# pas_pot_diff.net
KiCad netlist of a schematic drawn in EAGLE
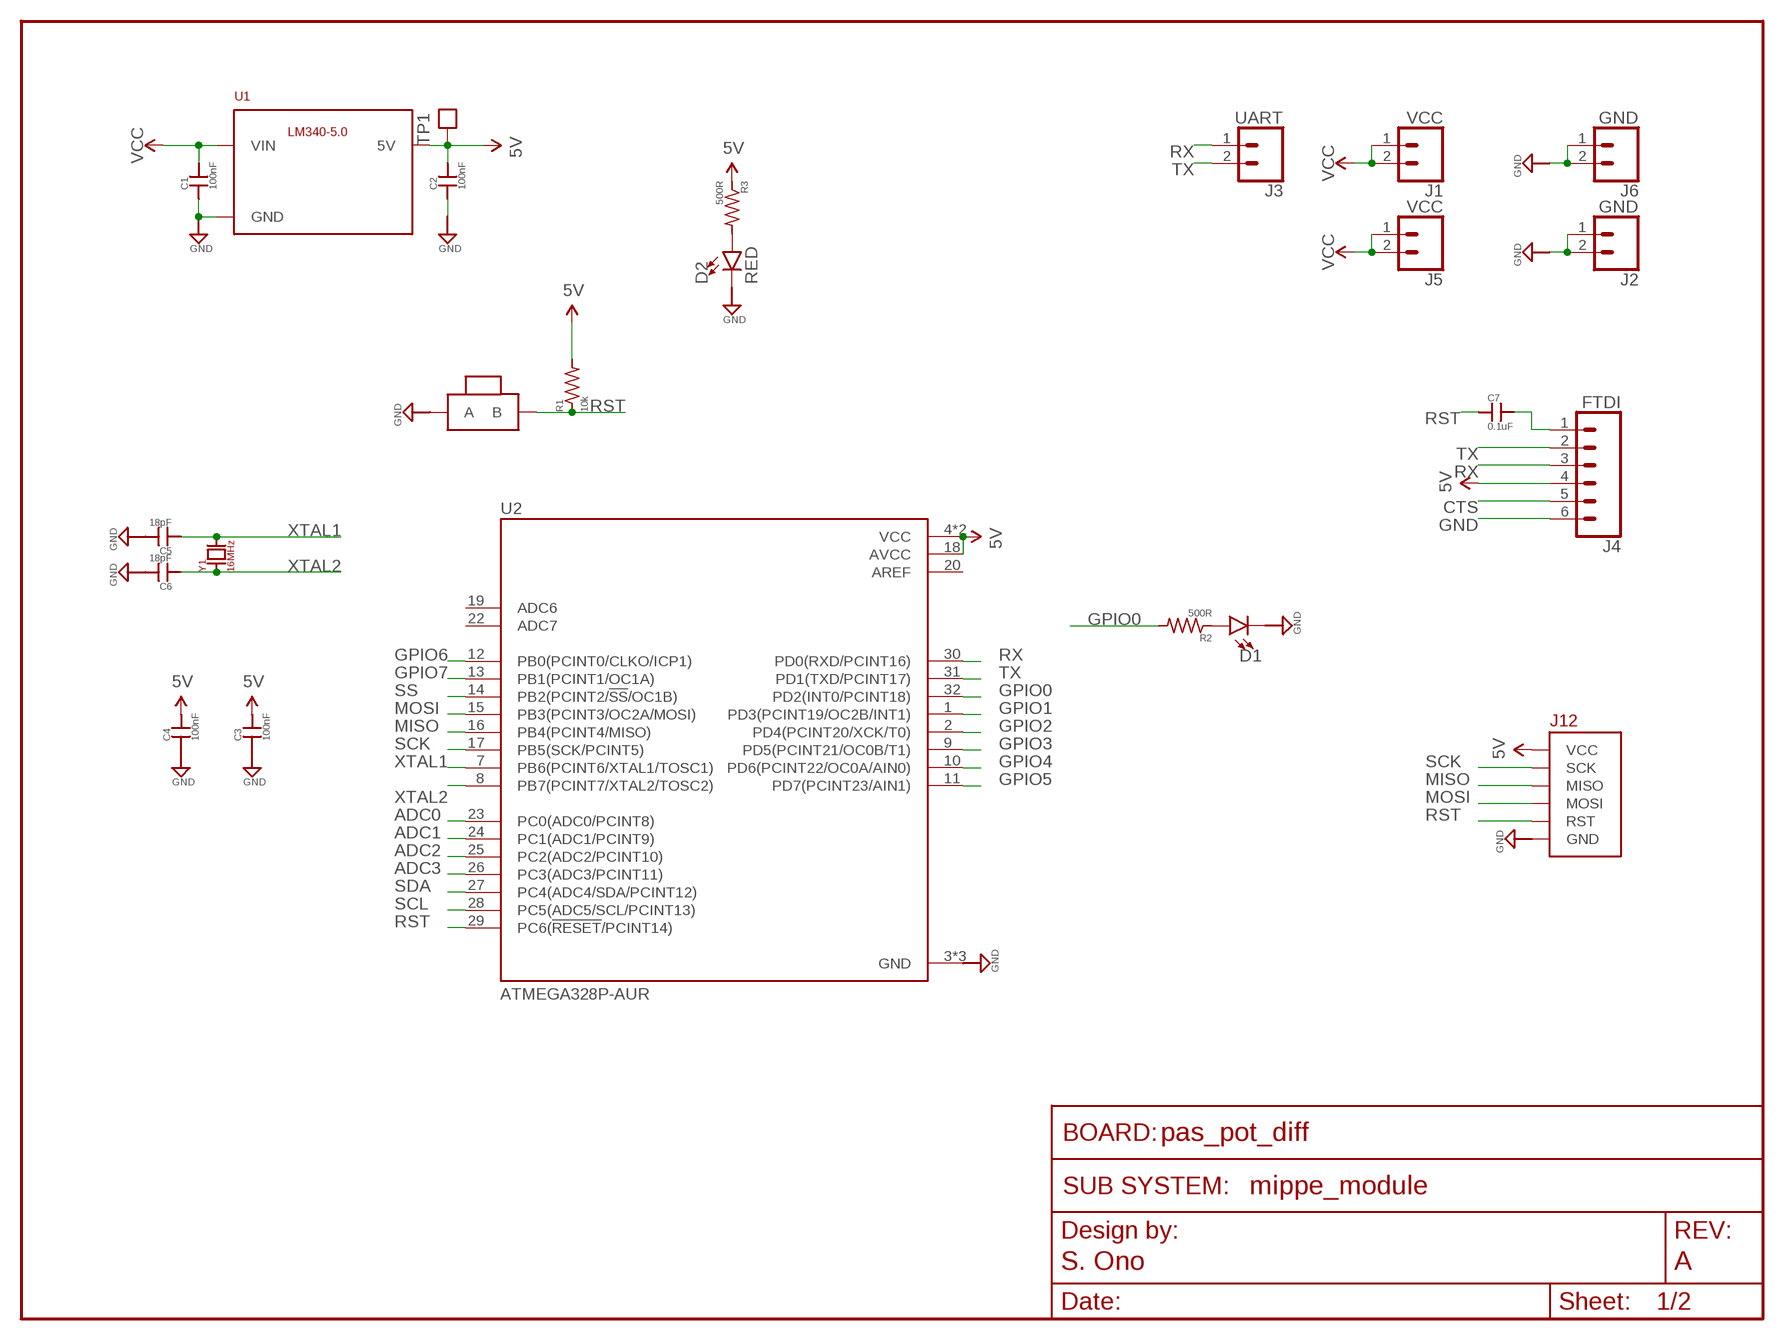
[diagram p0: schematic, sheet 1]
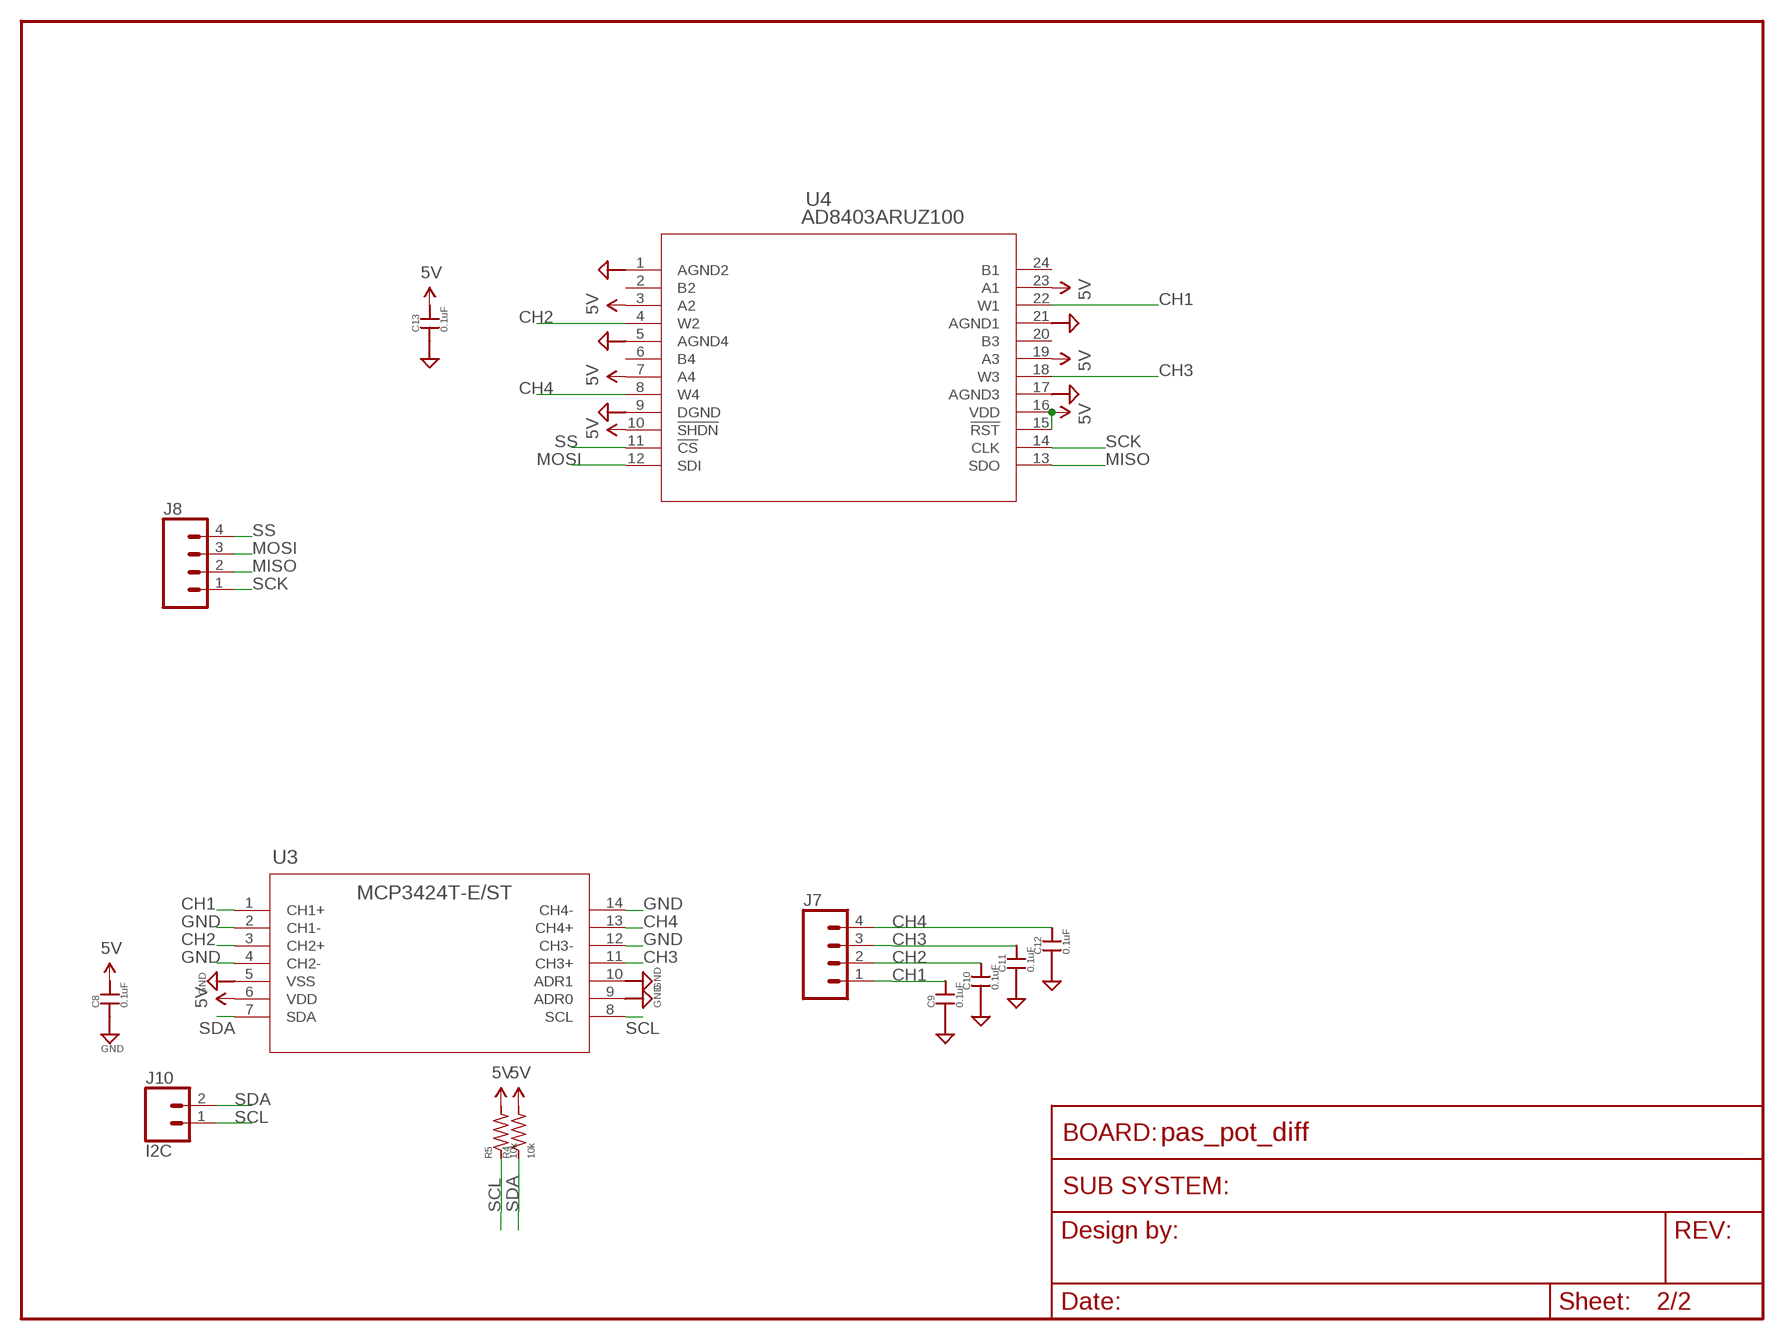
[diagram p1: schematic, sheet 2]

(export (version "E")
  (design (tool "Eeschema 10.0.6"))
  (components
    (comp (ref "C8")
      (value "0.1uF")
      (footprint "eagle-import:0402-CAP")
      (libsource (lib "eagle-import") (part "CAP0402-CAP"))
    )
    (comp (ref "C9")
      (value "0.1uF")
      (footprint "eagle-import:0402-CAP")
      (libsource (lib "eagle-import") (part "CAP0402-CAP"))
    )
    (comp (ref "C10")
      (value "0.1uF")
      (footprint "eagle-import:0402-CAP")
      (libsource (lib "eagle-import") (part "CAP0402-CAP"))
    )
    (comp (ref "C11")
      (value "0.1uF")
      (footprint "eagle-import:0402-CAP")
      (libsource (lib "eagle-import") (part "CAP0402-CAP"))
    )
    (comp (ref "C12")
      (value "0.1uF")
      (footprint "eagle-import:0402-CAP")
      (libsource (lib "eagle-import") (part "CAP0402-CAP"))
    )
    (comp (ref "C13")
      (value "0.1uF")
      (footprint "eagle-import:0402-CAP")
      (libsource (lib "eagle-import") (part "CAP0402-CAP"))
    )
    (comp (ref "J7")
      (value "CONN_04")
      (footprint "eagle-import:1X04")
      (libsource (lib "eagle-import") (part "CONN_04"))
    )
    (comp (ref "J8")
      (value "CONN_04")
      (footprint "eagle-import:1X04")
      (libsource (lib "eagle-import") (part "CONN_04"))
    )
    (comp (ref "J10")
      (value "I2C")
      (footprint "eagle-import:1X02")
      (libsource (lib "eagle-import") (part "CONN_02"))
    )
    (comp (ref "R4")
      (value "10k")
      (footprint "eagle-import:R0402")
      (libsource (lib "eagle-import") (part "R-US_R0402"))
    )
    (comp (ref "R5")
      (value "10k")
      (footprint "eagle-import:R0402")
      (libsource (lib "eagle-import") (part "R-US_R0402"))
    )
    (comp (ref "U3")
      (value "MCP3424T-E/ST")
      (footprint "eagle-import:TSSOP14_MC")
      (fields (field (name "MANUFACTURER_PART_NUMBER") "MCP3424TEST"))
      (libsource (lib "eagle-import") (part "MCP3424T-E/ST"))
    )
    (comp (ref "U4")
      (value "AD8403ARUZ100")
      (footprint "eagle-import:RU_24")
      (libsource (lib "eagle-import") (part "AD8403ARUZ100"))
    )
    (comp (ref "C1")
      (value "100nF")
      (footprint "eagle-import:0402-CAP")
      (libsource (lib "eagle-import") (part "CAP0402-CAP"))
    )
    (comp (ref "C2")
      (value "100nF")
      (footprint "eagle-import:0402-CAP")
      (libsource (lib "eagle-import") (part "CAP0402-CAP"))
    )
    (comp (ref "C3")
      (value "100nF")
      (footprint "eagle-import:0402-CAP")
      (libsource (lib "eagle-import") (part "CAP0402-CAP"))
    )
    (comp (ref "C4")
      (value "100nF")
      (footprint "eagle-import:0402-CAP")
      (libsource (lib "eagle-import") (part "CAP0402-CAP"))
    )
    (comp (ref "C5")
      (value "18pF")
      (footprint "eagle-import:0402-CAP")
      (libsource (lib "eagle-import") (part "CAP0402-CAP"))
    )
    (comp (ref "C6")
      (value "18pF")
      (footprint "eagle-import:0402-CAP")
      (libsource (lib "eagle-import") (part "CAP0402-CAP"))
    )
    (comp (ref "C7")
      (value "0.1uF")
      (footprint "eagle-import:0402-CAP")
      (libsource (lib "eagle-import") (part "CAP0402-CAP"))
    )
    (comp (ref "D1")
      (value "LED0603")
      (footprint "eagle-import:LED-0603")
      (libsource (lib "eagle-import") (part "LED0603"))
    )
    (comp (ref "D2")
      (value "RED")
      (footprint "eagle-import:LED-0603")
      (libsource (lib "eagle-import") (part "LED0603"))
    )
    (comp (ref "J1")
      (value "VCC")
      (footprint "eagle-import:1X02")
      (libsource (lib "eagle-import") (part "CONN_02"))
    )
    (comp (ref "J2")
      (value "GND")
      (footprint "eagle-import:1X02")
      (libsource (lib "eagle-import") (part "CONN_02"))
    )
    (comp (ref "J3")
      (value "UART")
      (footprint "eagle-import:1X02")
      (libsource (lib "eagle-import") (part "CONN_02"))
    )
    (comp (ref "J4")
      (value "FTDI")
      (footprint "eagle-import:1X06_NO_SILK")
      (libsource (lib "eagle-import") (part "CONN_06NO_SILK_FEMALE_PTH"))
    )
    (comp (ref "J5")
      (value "VCC")
      (footprint "eagle-import:1X02")
      (libsource (lib "eagle-import") (part "CONN_02"))
    )
    (comp (ref "J6")
      (value "GND")
      (footprint "eagle-import:1X02")
      (libsource (lib "eagle-import") (part "CONN_02"))
    )
    (comp (ref "J12")
      (value "BURNIN")
      (footprint "eagle-import:BURNIN")
      (libsource (lib "eagle-import") (part "BURNIN"))
    )
    (comp (ref "R1")
      (value "10k")
      (footprint "eagle-import:R0402")
      (libsource (lib "eagle-import") (part "R-US_R0402"))
    )
    (comp (ref "R2")
      (value "500R")
      (footprint "eagle-import:R0402")
      (libsource (lib "eagle-import") (part "R-US_R0402"))
    )
    (comp (ref "R3")
      (value "500R")
      (footprint "eagle-import:R0402")
      (libsource (lib "eagle-import") (part "R-US_R0402"))
    )
    (comp (ref "SW1")
      (value "BTN-PTS810")
      (footprint "eagle-import:BTN_PTS810")
      (libsource (lib "eagle-import") (part "BTN-PTS810"))
    )
    (comp (ref "TP1")
      (value "TEST_POINTTHRU")
      (footprint "eagle-import:TEST_POINT")
      (libsource (lib "eagle-import") (part "TEST_POINTTHRU"))
    )
    (comp (ref "U1")
      (value "LM340MPX-5.0230")
      (footprint "eagle-import:SOT230P700X180-4N")
      (libsource (lib "eagle-import") (part "LM340MPX-5.0230"))
    )
    (comp (ref "U2")
      (value "ATMEGA328P-AUR")
      (footprint "eagle-import:QFP80P900X900X120-32N")
      (fields (field (name "DIGI-KEY_PART_NUMBER") "ATMEGA328P-AURCT-ND") (field (name "MF") "Microchip"))
      (libsource (lib "eagle-import") (part "ATMEGA328P-AUR"))
    )
    (comp (ref "Y1")
      (value "16MHz")
      (footprint "eagle-import:XTAL500X320X130N")
      (libsource (lib "eagle-import") (part "CRYSTAL_SMOL"))
    )
  )
  (nets
    (net (code "1") (name "5V") (class "Default")
      (node (ref "C13") (pin "2") (pinfunction "2_2") (pintype "passive"))
      (node (ref "C2") (pin "2") (pinfunction "2_2") (pintype "passive"))
      (node (ref "C3") (pin "2") (pinfunction "2_2") (pintype "passive"))
      (node (ref "C4") (pin "2") (pinfunction "2_2") (pintype "passive"))
      (node (ref "C8") (pin "2") (pinfunction "2_2") (pintype "passive"))
      (node (ref "J12") (pin "3.3V") (pinfunction "VCC_3.3V") (pintype "power_in"))
      (node (ref "J4") (pin "4") (pinfunction "4_4") (pintype "passive"))
      (node (ref "R1") (pin "2") (pinfunction "2_2") (pintype "passive"))
      (node (ref "R3") (pin "1") (pinfunction "1_1") (pintype "passive"))
      (node (ref "R4") (pin "2") (pinfunction "2_2") (pintype "passive"))
      (node (ref "R5") (pin "2") (pinfunction "2_2") (pintype "passive"))
      (node (ref "TP1") (pin "1") (pinfunction "P$1_1") (pintype "bidirectional"))
      (node (ref "U1") (pin "3") (pinfunction "5V_3") (pintype "power_in"))
      (node (ref "U2") (pin "18") (pinfunction "AVCC_18") (pintype "power_in"))
      (node (ref "U2") (pin "4") (pinfunction "VCC_4") (pintype "power_in"))
      (node (ref "U2") (pin "6") (pinfunction "VCC_6") (pintype "power_in"))
      (node (ref "U3") (pin "6") (pinfunction "VDD_6") (pintype "power_in"))
      (node (ref "U4") (pin "10") (pinfunction "~{SHDN}_10") (pintype "passive"))
      (node (ref "U4") (pin "15") (pinfunction "~{RST}_15") (pintype "passive"))
      (node (ref "U4") (pin "16") (pinfunction "VDD_16") (pintype "power_in"))
      (node (ref "U4") (pin "19") (pinfunction "A3_19") (pintype "passive"))
      (node (ref "U4") (pin "23") (pinfunction "A1_23") (pintype "passive"))
      (node (ref "U4") (pin "3") (pinfunction "A2_3") (pintype "passive"))
      (node (ref "U4") (pin "7") (pinfunction "A4_7") (pintype "passive"))
    )
    (net (code "2") (name "ADC0") (class "Default")
      (node (ref "U2") (pin "23") (pinfunction "PC0(ADC0/PCINT8)_23") (pintype "bidirectional"))
    )
    (net (code "3") (name "ADC1") (class "Default")
      (node (ref "U2") (pin "24") (pinfunction "PC1(ADC1/PCINT9)_24") (pintype "bidirectional"))
    )
    (net (code "4") (name "ADC2") (class "Default")
      (node (ref "U2") (pin "25") (pinfunction "PC2(ADC2/PCINT10)_25") (pintype "bidirectional"))
    )
    (net (code "5") (name "ADC3") (class "Default")
      (node (ref "U2") (pin "26") (pinfunction "PC3(ADC3/PCINT11)_26") (pintype "bidirectional"))
    )
    (net (code "6") (name "AREF") (class "Default")
      (node (ref "U2") (pin "20") (pinfunction "AREF_20") (pintype "power_in"))
    )
    (net (code "7") (name "CH1") (class "Default")
      (node (ref "C9") (pin "2") (pinfunction "2_2") (pintype "passive"))
      (node (ref "J7") (pin "1") (pinfunction "1_1") (pintype "passive"))
      (node (ref "U3") (pin "1") (pinfunction "CH1+_1") (pintype "input"))
      (node (ref "U4") (pin "22") (pinfunction "W1_22") (pintype "passive"))
    )
    (net (code "8") (name "CH2") (class "Default")
      (node (ref "C10") (pin "2") (pinfunction "2_2") (pintype "passive"))
      (node (ref "J7") (pin "2") (pinfunction "2_2") (pintype "passive"))
      (node (ref "U3") (pin "3") (pinfunction "CH2+_3") (pintype "input"))
      (node (ref "U4") (pin "4") (pinfunction "W2_4") (pintype "passive"))
    )
    (net (code "9") (name "CH3") (class "Default")
      (node (ref "C11") (pin "2") (pinfunction "2_2") (pintype "passive"))
      (node (ref "J7") (pin "3") (pinfunction "3_3") (pintype "passive"))
      (node (ref "U3") (pin "11") (pinfunction "CH3+_11") (pintype "input"))
      (node (ref "U4") (pin "18") (pinfunction "W3_18") (pintype "passive"))
    )
    (net (code "10") (name "CH4") (class "Default")
      (node (ref "C12") (pin "2") (pinfunction "2_2") (pintype "passive"))
      (node (ref "J7") (pin "4") (pinfunction "4_4") (pintype "passive"))
      (node (ref "U3") (pin "13") (pinfunction "CH4+_13") (pintype "input"))
      (node (ref "U4") (pin "8") (pinfunction "W4_8") (pintype "passive"))
    )
    (net (code "11") (name "CTS") (class "Default")
      (node (ref "J4") (pin "5") (pinfunction "5_5") (pintype "passive"))
    )
    (net (code "12") (name "GND") (class "Default")
      (node (ref "C1") (pin "1") (pinfunction "1_1") (pintype "passive"))
      (node (ref "C10") (pin "1") (pinfunction "1_1") (pintype "passive"))
      (node (ref "C11") (pin "1") (pinfunction "1_1") (pintype "passive"))
      (node (ref "C12") (pin "1") (pinfunction "1_1") (pintype "passive"))
      (node (ref "C13") (pin "1") (pinfunction "1_1") (pintype "passive"))
      (node (ref "C2") (pin "1") (pinfunction "1_1") (pintype "passive"))
      (node (ref "C3") (pin "1") (pinfunction "1_1") (pintype "passive"))
      (node (ref "C4") (pin "1") (pinfunction "1_1") (pintype "passive"))
      (node (ref "C5") (pin "2") (pinfunction "2_2") (pintype "passive"))
      (node (ref "C6") (pin "2") (pinfunction "2_2") (pintype "passive"))
      (node (ref "C8") (pin "1") (pinfunction "1_1") (pintype "passive"))
      (node (ref "C9") (pin "1") (pinfunction "1_1") (pintype "passive"))
      (node (ref "D1") (pin "C") (pinfunction "C_C") (pintype "passive"))
      (node (ref "D2") (pin "C") (pinfunction "C_C") (pintype "passive"))
      (node (ref "J12") (pin "GND") (pinfunction "GND_GND") (pintype "power_in"))
      (node (ref "J2") (pin "1") (pinfunction "1_1") (pintype "passive"))
      (node (ref "J2") (pin "2") (pinfunction "2_2") (pintype "passive"))
      (node (ref "J4") (pin "6") (pinfunction "6_6") (pintype "passive"))
      (node (ref "J6") (pin "1") (pinfunction "1_1") (pintype "passive"))
      (node (ref "J6") (pin "2") (pinfunction "2_2") (pintype "passive"))
      (node (ref "SW1") (pin "1") (pinfunction "A_1") (pintype "bidirectional"))
      (node (ref "SW1") (pin "2") (pinfunction "A_2") (pintype "bidirectional"))
      (node (ref "U1") (pin "2") (pinfunction "GND_2") (pintype "power_in"))
      (node (ref "U1") (pin "4") (pinfunction "GND_4") (pintype "power_in"))
      (node (ref "U2") (pin "21") (pinfunction "GND_21") (pintype "power_in"))
      (node (ref "U2") (pin "3") (pinfunction "GND_3") (pintype "power_in"))
      (node (ref "U2") (pin "5") (pinfunction "GND_5") (pintype "power_in"))
      (node (ref "U3") (pin "10") (pinfunction "ADR1_10") (pintype "passive"))
      (node (ref "U3") (pin "12") (pinfunction "CH3-_12") (pintype "input"))
      (node (ref "U3") (pin "14") (pinfunction "CH4-_14") (pintype "input"))
      (node (ref "U3") (pin "2") (pinfunction "CH1-_2") (pintype "input"))
      (node (ref "U3") (pin "4") (pinfunction "CH2-_4") (pintype "input"))
      (node (ref "U3") (pin "5") (pinfunction "VSS_5") (pintype "power_in"))
      (node (ref "U3") (pin "9") (pinfunction "ADR0_9") (pintype "passive"))
      (node (ref "U4") (pin "1") (pinfunction "AGND2_1") (pintype "passive"))
      (node (ref "U4") (pin "17") (pinfunction "AGND3_17") (pintype "passive"))
      (node (ref "U4") (pin "21") (pinfunction "AGND1_21") (pintype "passive"))
      (node (ref "U4") (pin "5") (pinfunction "AGND4_5") (pintype "passive"))
      (node (ref "U4") (pin "9") (pinfunction "DGND_9") (pintype "passive"))
    )
    (net (code "13") (name "GPIO0") (class "Default")
      (node (ref "R2") (pin "2") (pinfunction "2_2") (pintype "passive"))
      (node (ref "U2") (pin "32") (pinfunction "PD2(INT0/PCINT18)_32") (pintype "bidirectional"))
    )
    (net (code "14") (name "GPIO1") (class "Default")
      (node (ref "U2") (pin "1") (pinfunction "PD3(PCINT19/OC2B/INT1)_1") (pintype "bidirectional"))
    )
    (net (code "15") (name "GPIO2") (class "Default")
      (node (ref "U2") (pin "2") (pinfunction "PD4(PCINT20/XCK/T0)_2") (pintype "bidirectional"))
    )
    (net (code "16") (name "GPIO3") (class "Default")
      (node (ref "U2") (pin "9") (pinfunction "PD5(PCINT21/OC0B/T1)_9") (pintype "bidirectional"))
    )
    (net (code "17") (name "GPIO4") (class "Default")
      (node (ref "U2") (pin "10") (pinfunction "PD6(PCINT22/OC0A/AIN0)_10") (pintype "bidirectional"))
    )
    (net (code "18") (name "GPIO5") (class "Default")
      (node (ref "U2") (pin "11") (pinfunction "PD7(PCINT23/AIN1)_11") (pintype "bidirectional"))
    )
    (net (code "19") (name "GPIO6") (class "Default")
      (node (ref "U2") (pin "12") (pinfunction "PB0(PCINT0/CLKO/ICP1)_12") (pintype "bidirectional"))
    )
    (net (code "20") (name "GPIO7") (class "Default")
      (node (ref "U2") (pin "13") (pinfunction "PB1(PCINT1/OC1A)_13") (pintype "bidirectional"))
    )
    (net (code "21") (name "MISO") (class "Default")
      (node (ref "J12") (pin "MISO") (pinfunction "MISO_MISO") (pintype "bidirectional"))
      (node (ref "J8") (pin "2") (pinfunction "2_2") (pintype "passive"))
      (node (ref "U2") (pin "16") (pinfunction "PB4(PCINT4/MISO)_16") (pintype "bidirectional"))
      (node (ref "U4") (pin "13") (pinfunction "SDO_13") (pintype "passive"))
    )
    (net (code "22") (name "MOSI") (class "Default")
      (node (ref "J12") (pin "MOSI") (pinfunction "MOSI_MOSI") (pintype "bidirectional"))
      (node (ref "J8") (pin "3") (pinfunction "3_3") (pintype "passive"))
      (node (ref "U2") (pin "15") (pinfunction "PB3(PCINT3/OC2A/MOSI)_15") (pintype "bidirectional"))
      (node (ref "U4") (pin "12") (pinfunction "SDI_12") (pintype "passive"))
    )
    (net (code "23") (name "Net-(C7-Pad2)") (class "Default")
      (node (ref "C7") (pin "2") (pinfunction "2_2") (pintype "passive"))
      (node (ref "J4") (pin "1") (pinfunction "1_1") (pintype "passive"))
    )
    (net (code "24") (name "Net-(D1-PadA)") (class "Default")
      (node (ref "D1") (pin "A") (pinfunction "A_A") (pintype "passive"))
      (node (ref "R2") (pin "1") (pinfunction "1_1") (pintype "passive"))
    )
    (net (code "25") (name "Net-(D2-PadA)") (class "Default")
      (node (ref "D2") (pin "A") (pinfunction "A_A") (pintype "passive"))
      (node (ref "R3") (pin "2") (pinfunction "2_2") (pintype "passive"))
    )
    (net (code "26") (name "RST") (class "Default")
      (node (ref "C7") (pin "1") (pinfunction "1_1") (pintype "passive"))
      (node (ref "J12") (pin "RST") (pinfunction "RST_RST") (pintype "bidirectional"))
      (node (ref "R1") (pin "1") (pinfunction "1_1") (pintype "passive"))
      (node (ref "SW1") (pin "3") (pinfunction "B_3") (pintype "bidirectional"))
      (node (ref "SW1") (pin "4") (pinfunction "B_4") (pintype "bidirectional"))
      (node (ref "U2") (pin "29") (pinfunction "PC6(~{RESET}/PCINT14)_29") (pintype "bidirectional"))
    )
    (net (code "27") (name "RX") (class "Default")
      (node (ref "J3") (pin "1") (pinfunction "1_1") (pintype "passive"))
      (node (ref "J4") (pin "3") (pinfunction "3_3") (pintype "passive"))
      (node (ref "U2") (pin "30") (pinfunction "PD0(RXD/PCINT16)_30") (pintype "bidirectional"))
    )
    (net (code "28") (name "SCK") (class "Default")
      (node (ref "J12") (pin "SCK") (pinfunction "SCK_SCK") (pintype "bidirectional"))
      (node (ref "J8") (pin "1") (pinfunction "1_1") (pintype "passive"))
      (node (ref "U2") (pin "17") (pinfunction "PB5(SCK/PCINT5)_17") (pintype "bidirectional"))
      (node (ref "U4") (pin "14") (pinfunction "CLK_14") (pintype "passive"))
    )
    (net (code "29") (name "SCL") (class "Default")
      (node (ref "J10") (pin "1") (pinfunction "1_1") (pintype "passive"))
      (node (ref "R5") (pin "1") (pinfunction "1_1") (pintype "passive"))
      (node (ref "U2") (pin "28") (pinfunction "PC5(ADC5/SCL/PCINT13)_28") (pintype "bidirectional"))
      (node (ref "U3") (pin "8") (pinfunction "SCL_8") (pintype "input"))
    )
    (net (code "30") (name "SDA") (class "Default")
      (node (ref "J10") (pin "2") (pinfunction "2_2") (pintype "passive"))
      (node (ref "R4") (pin "1") (pinfunction "1_1") (pintype "passive"))
      (node (ref "U2") (pin "27") (pinfunction "PC4(ADC4/SDA/PCINT12)_27") (pintype "bidirectional"))
      (node (ref "U3") (pin "7") (pinfunction "SDA_7") (pintype "bidirectional"))
    )
    (net (code "31") (name "SS") (class "Default")
      (node (ref "J8") (pin "4") (pinfunction "4_4") (pintype "passive"))
      (node (ref "U2") (pin "14") (pinfunction "PB2(PCINT2/~{SS}/OC1B)_14") (pintype "bidirectional"))
      (node (ref "U4") (pin "11") (pinfunction "~{CS}_11") (pintype "passive"))
    )
    (net (code "32") (name "TX") (class "Default")
      (node (ref "J3") (pin "2") (pinfunction "2_2") (pintype "passive"))
      (node (ref "J4") (pin "2") (pinfunction "2_2") (pintype "passive"))
      (node (ref "U2") (pin "31") (pinfunction "PD1(TXD/PCINT17)_31") (pintype "bidirectional"))
    )
    (net (code "33") (name "VCC") (class "Default")
      (node (ref "C1") (pin "2") (pinfunction "2_2") (pintype "passive"))
      (node (ref "J1") (pin "1") (pinfunction "1_1") (pintype "passive"))
      (node (ref "J1") (pin "2") (pinfunction "2_2") (pintype "passive"))
      (node (ref "J5") (pin "1") (pinfunction "1_1") (pintype "passive"))
      (node (ref "J5") (pin "2") (pinfunction "2_2") (pintype "passive"))
      (node (ref "U1") (pin "1") (pinfunction "VIN_1") (pintype "power_in"))
    )
    (net (code "34") (name "XTAL1") (class "Default")
      (node (ref "C5") (pin "1") (pinfunction "1_1") (pintype "passive"))
      (node (ref "U2") (pin "7") (pinfunction "PB6(PCINT6/XTAL1/TOSC1)_7") (pintype "bidirectional"))
      (node (ref "Y1") (pin "2") (pinfunction "B_2") (pintype "passive"))
    )
    (net (code "35") (name "XTAL2") (class "Default")
      (node (ref "C6") (pin "1") (pinfunction "1_1") (pintype "passive"))
      (node (ref "U2") (pin "8") (pinfunction "PB7(PCINT7/XTAL2/TOSC2)_8") (pintype "bidirectional"))
      (node (ref "Y1") (pin "1") (pinfunction "A_1") (pintype "passive"))
    )
    (net (code "36") (name "unconnected-(U2-ADC6-Pad19)") (class "Default")
      (node (ref "U2") (pin "19") (pinfunction "ADC6_19") (pintype "input"))
    )
    (net (code "37") (name "unconnected-(U2-ADC7-Pad22)") (class "Default")
      (node (ref "U2") (pin "22") (pinfunction "ADC7_22") (pintype "input"))
    )
    (net (code "38") (name "unconnected-(U4-B1-Pad24)") (class "Default")
      (node (ref "U4") (pin "24") (pinfunction "B1_24") (pintype "passive"))
    )
    (net (code "39") (name "unconnected-(U4-B2-Pad2)") (class "Default")
      (node (ref "U4") (pin "2") (pinfunction "B2_2") (pintype "passive"))
    )
    (net (code "40") (name "unconnected-(U4-B3-Pad20)") (class "Default")
      (node (ref "U4") (pin "20") (pinfunction "B3_20") (pintype "passive"))
    )
    (net (code "41") (name "unconnected-(U4-B4-Pad6)") (class "Default")
      (node (ref "U4") (pin "6") (pinfunction "B4_6") (pintype "passive"))
    )
  )
)
